# moire_brd_eagle7.net
KiCad netlist of a schematic drawn in EAGLE
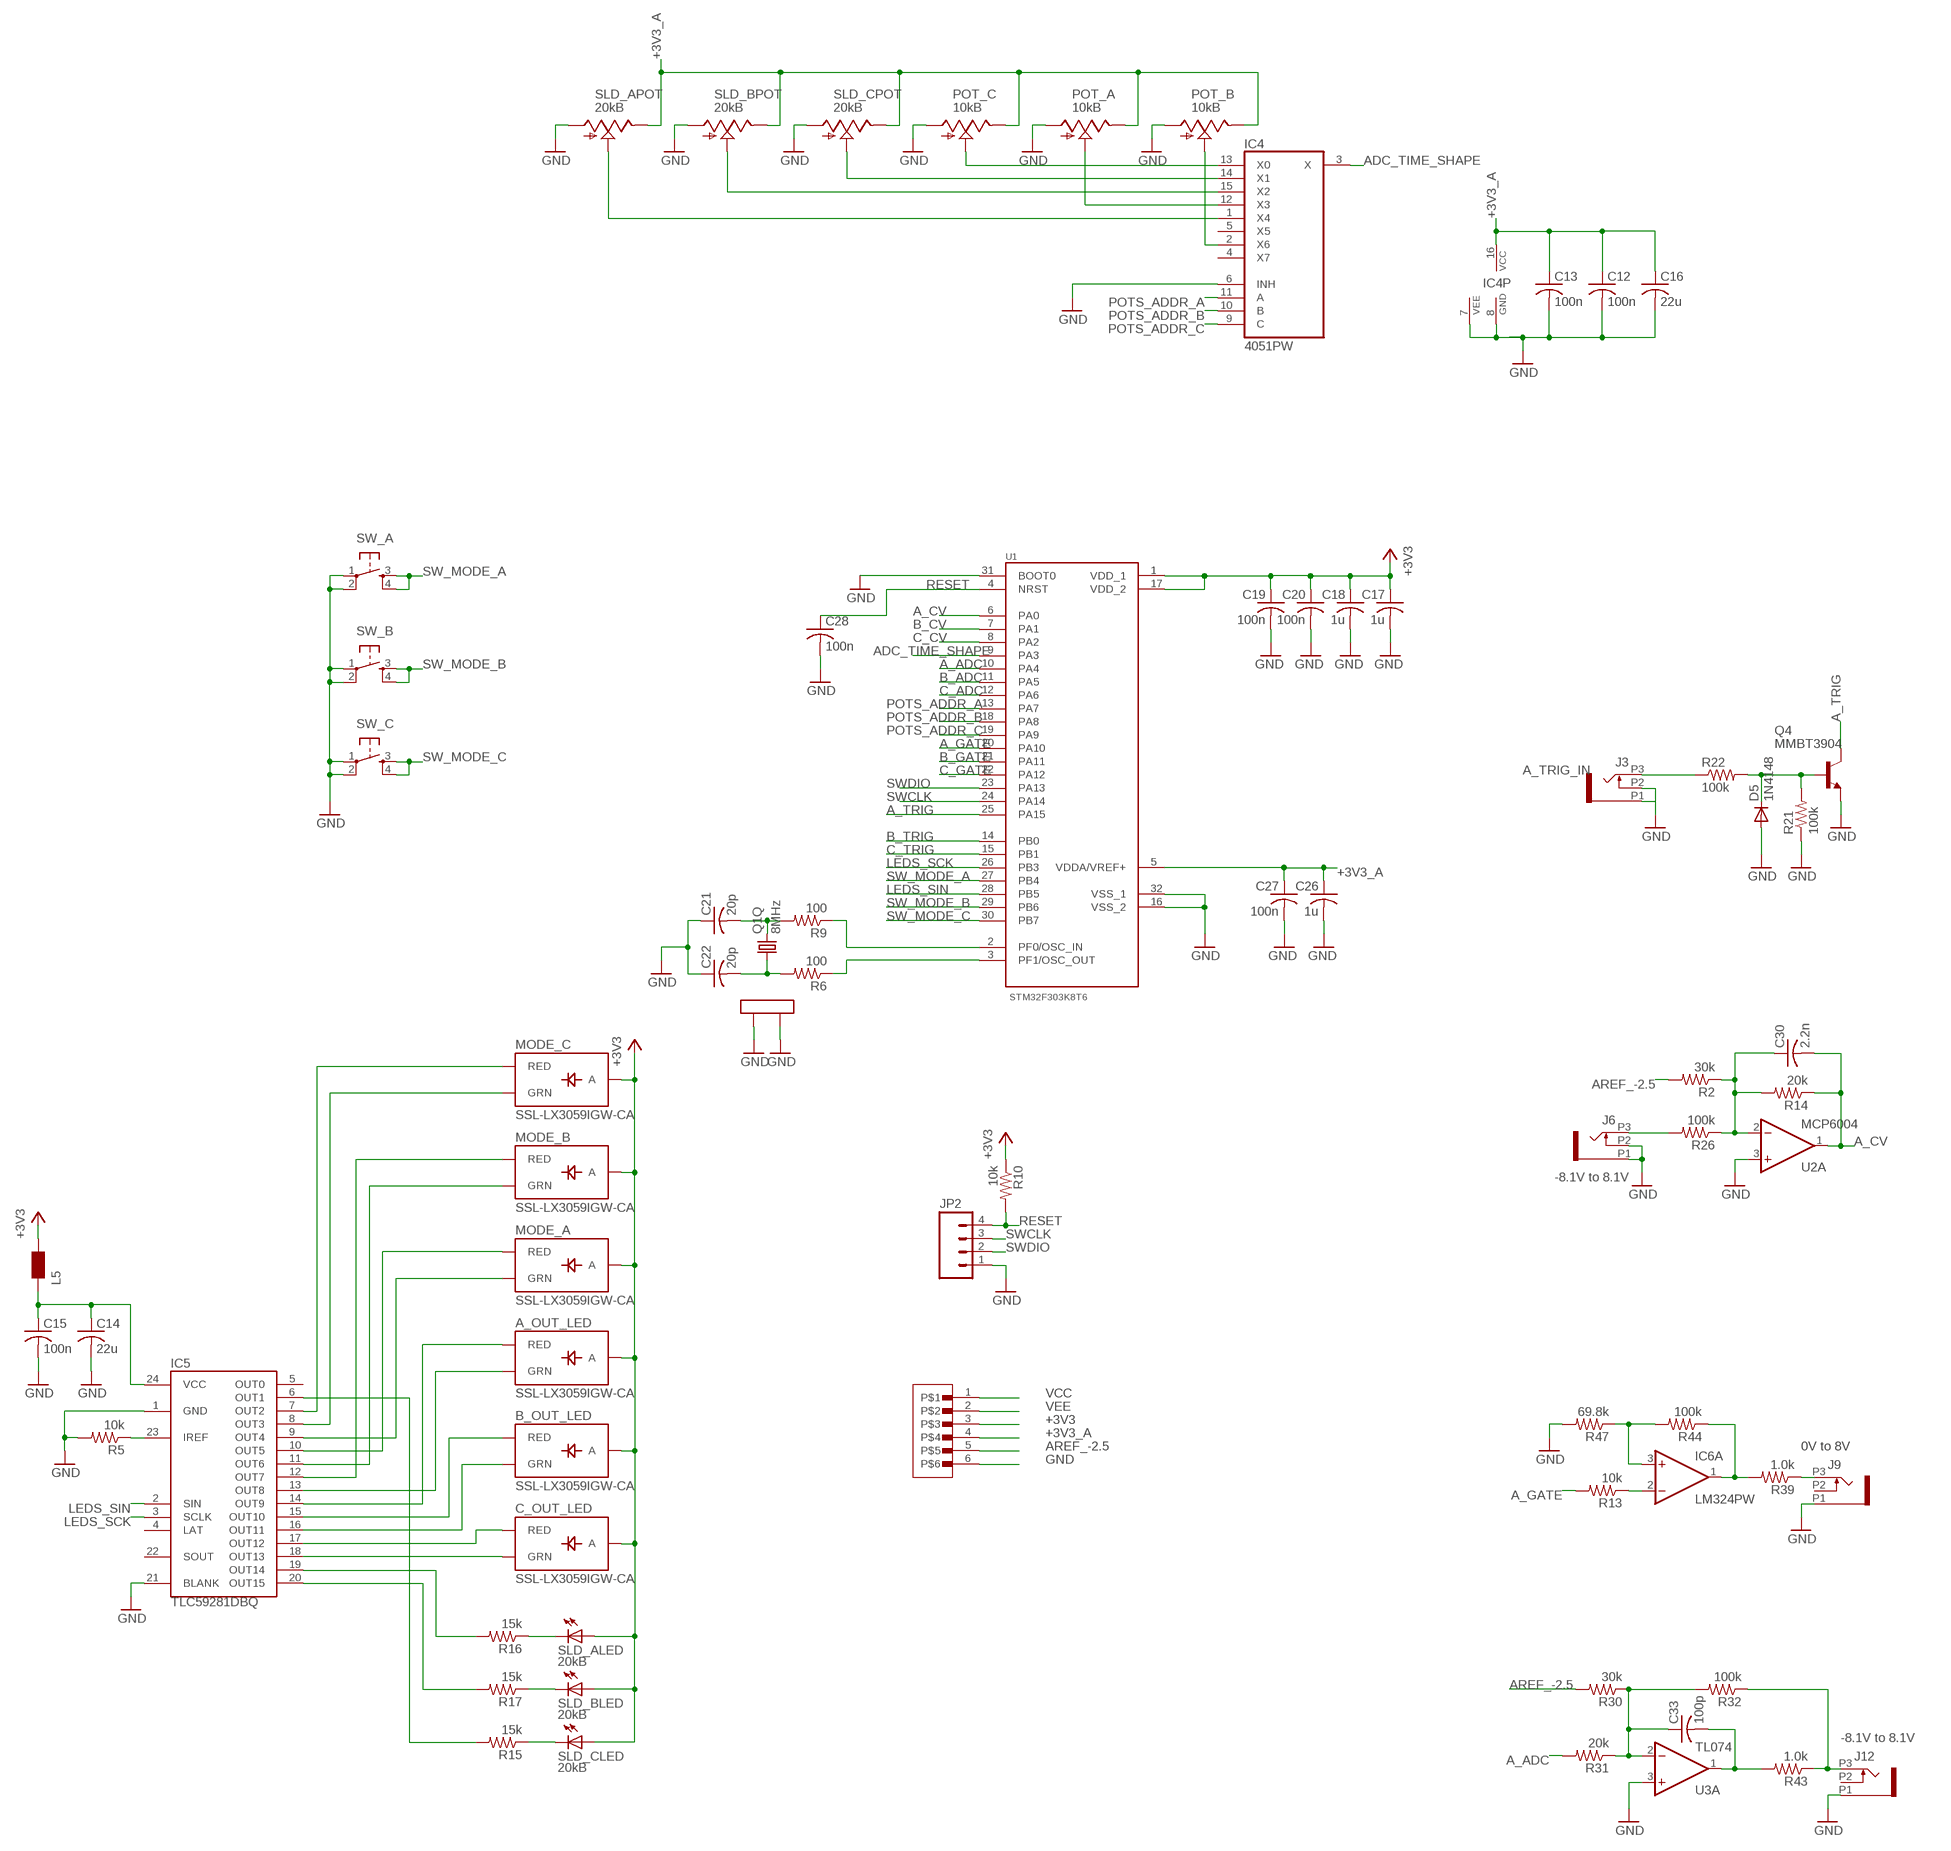
[diagram p0: schematic, sheet 1, part 1 of 2]
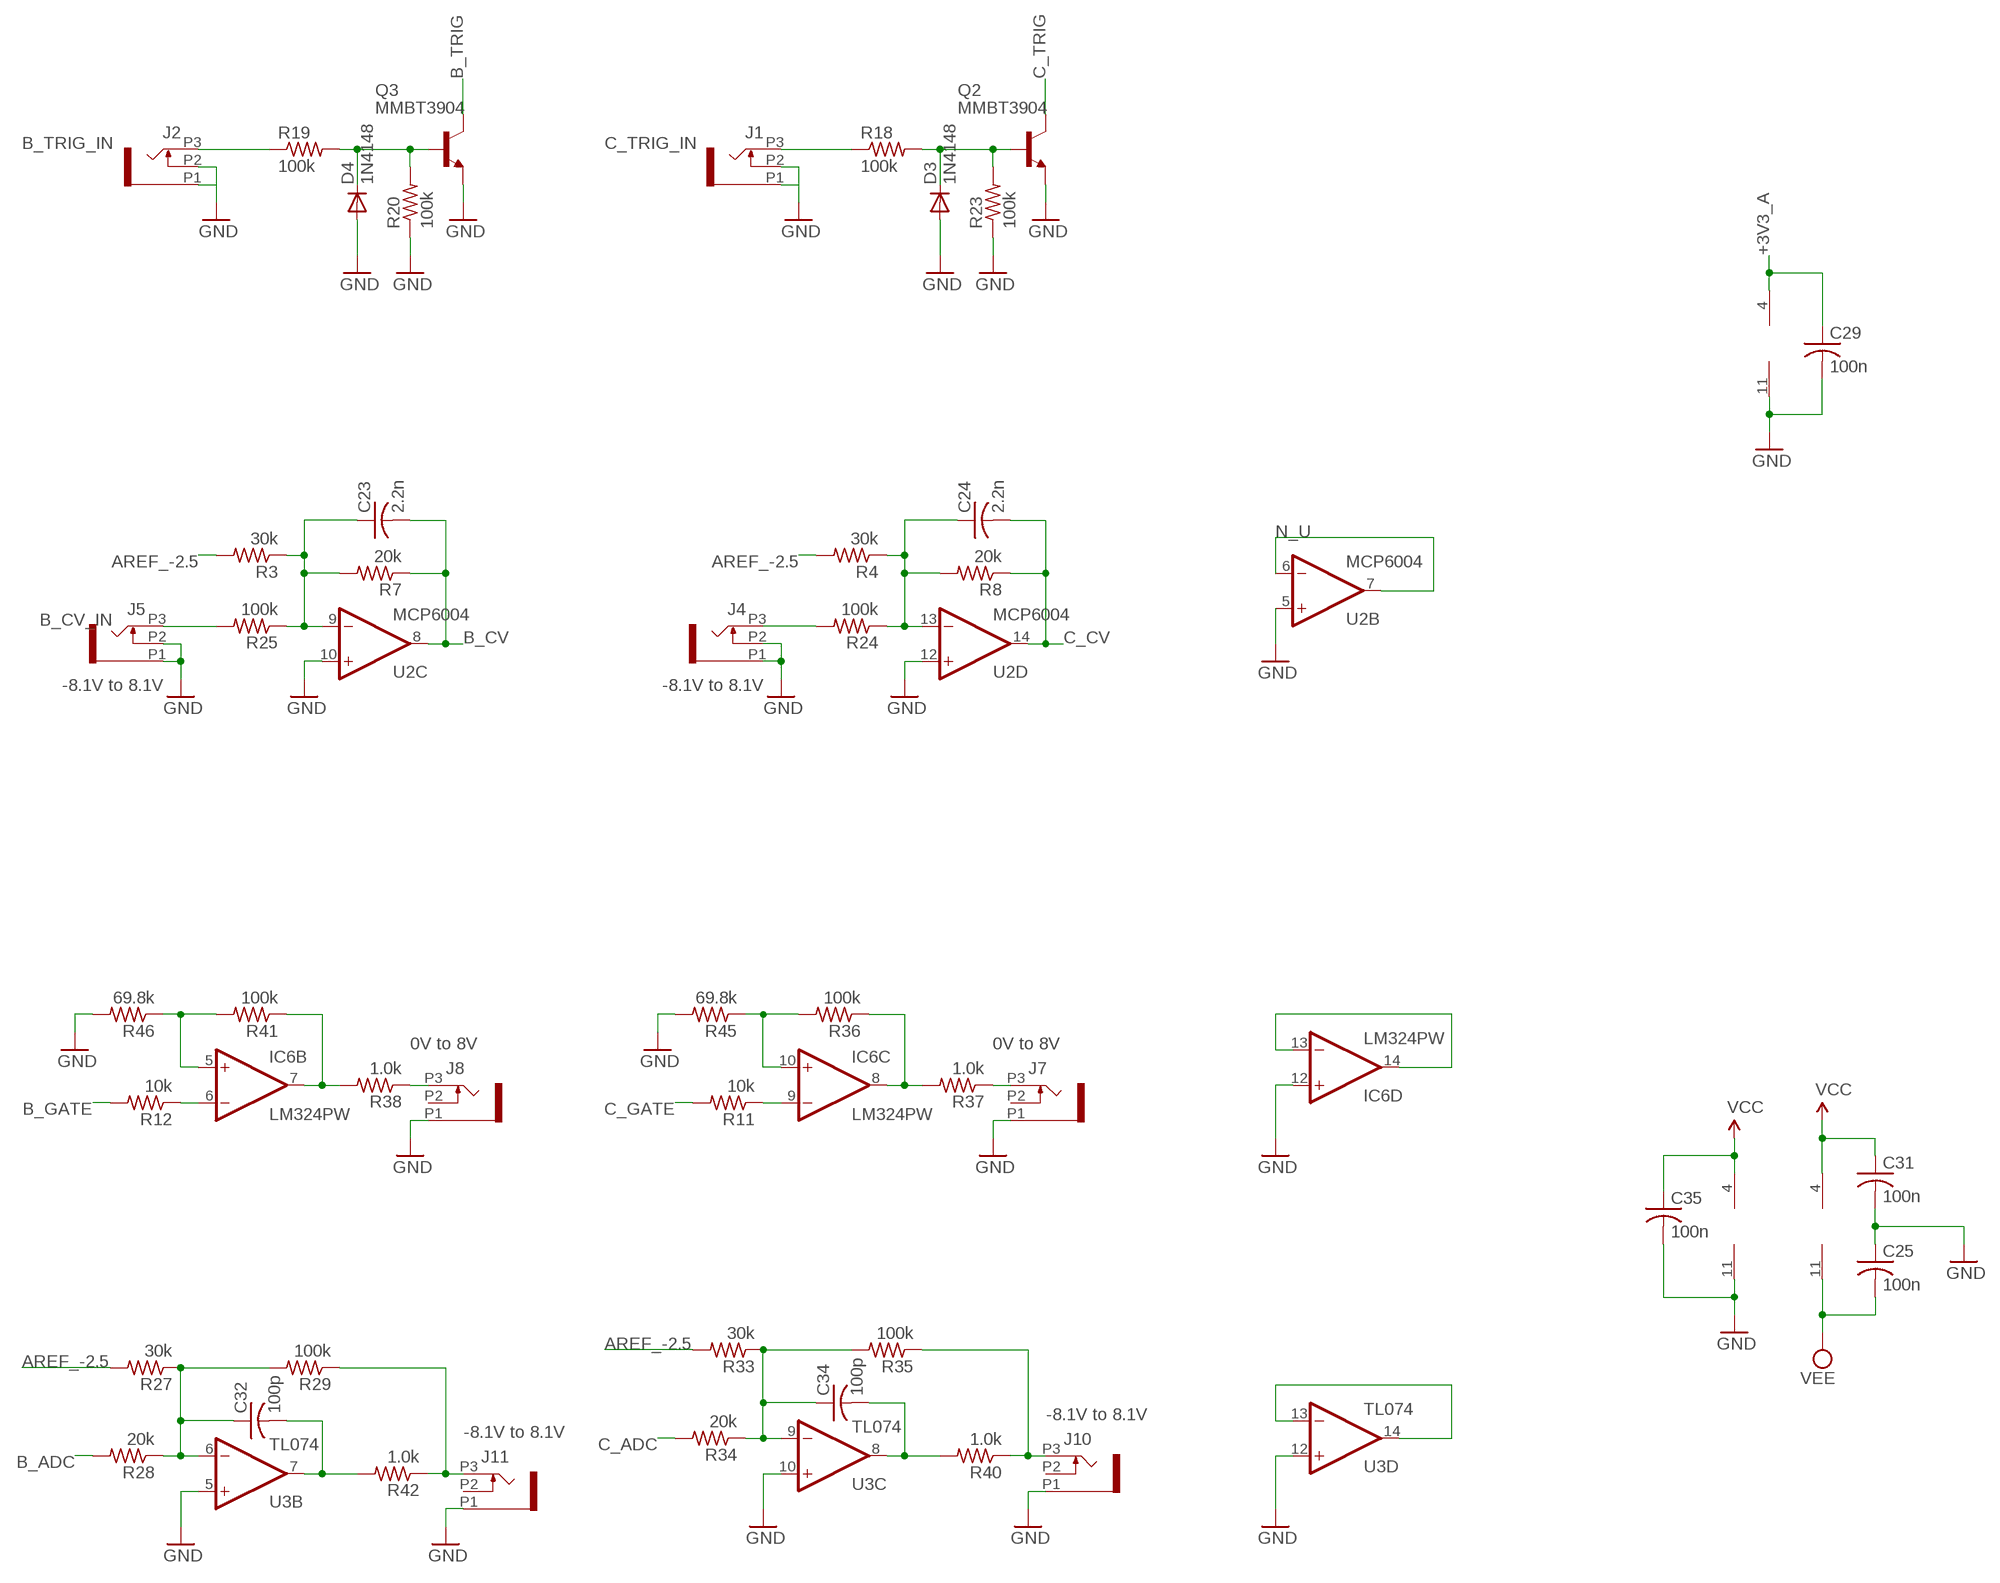
[diagram p1: schematic, sheet 1, part 2 of 2]
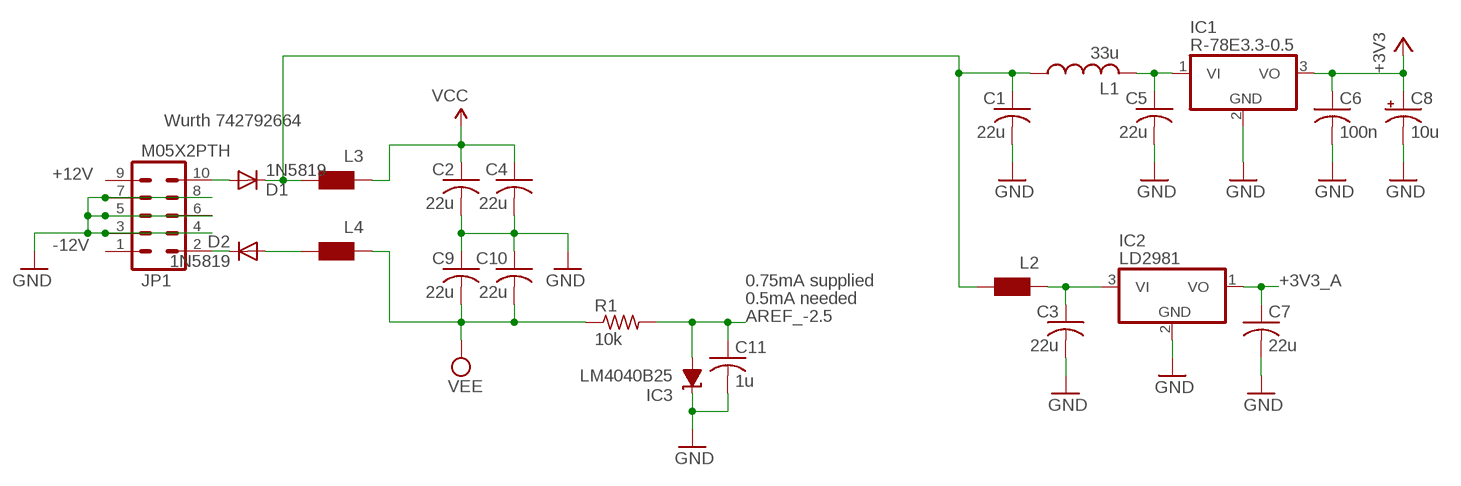
[diagram p2: schematic, sheet 2]

(export (version "E")
  (design (tool "Eeschema 10.0.6"))
  (components
    (comp (ref "A_OUT_LED")
      (value "SSL-LX3059IGW-CA")
      (footprint "eagle-import:LED-BICOLOR-THROUGHHOLE-LUMEX")
      (libsource (lib "eagle-import") (part "LED-BICOLOR-THROUGHHOLE-CA"))
    )
    (comp (ref "B_OUT_LED")
      (value "SSL-LX3059IGW-CA")
      (footprint "eagle-import:LED-BICOLOR-THROUGHHOLE-LUMEX")
      (libsource (lib "eagle-import") (part "LED-BICOLOR-THROUGHHOLE-CA"))
    )
    (comp (ref "C12")
      (value "100n")
      (footprint "eagle-import:RCL_C0603")
      (libsource (lib "eagle-import") (part "RCL_C-USC0603"))
    )
    (comp (ref "C13")
      (value "100n")
      (footprint "eagle-import:RCL_C0603")
      (libsource (lib "eagle-import") (part "RCL_C-USC0603"))
    )
    (comp (ref "C14")
      (value "22u")
      (footprint "eagle-import:RCL_C1206")
      (libsource (lib "eagle-import") (part "RCL_C-USC1206"))
    )
    (comp (ref "C15")
      (value "100n")
      (footprint "eagle-import:RCL_C0603")
      (libsource (lib "eagle-import") (part "RCL_C-USC0603"))
    )
    (comp (ref "C16")
      (value "22u")
      (footprint "eagle-import:RCL_C1206")
      (libsource (lib "eagle-import") (part "RCL_C-USC1206"))
    )
    (comp (ref "C17")
      (value "1u")
      (footprint "eagle-import:RCL_C0603")
      (libsource (lib "eagle-import") (part "RCL_C-USC0603"))
    )
    (comp (ref "C18")
      (value "1u")
      (footprint "eagle-import:RCL_C0603")
      (libsource (lib "eagle-import") (part "RCL_C-USC0603"))
    )
    (comp (ref "C19")
      (value "100n")
      (footprint "eagle-import:RCL_C0603")
      (libsource (lib "eagle-import") (part "RCL_C-USC0603"))
    )
    (comp (ref "C20")
      (value "100n")
      (footprint "eagle-import:RCL_C0603")
      (libsource (lib "eagle-import") (part "RCL_C-USC0603"))
    )
    (comp (ref "C21")
      (value "20p")
      (footprint "eagle-import:RCL_C0603")
      (libsource (lib "eagle-import") (part "RCL_C-USC0603"))
    )
    (comp (ref "C22")
      (value "20p")
      (footprint "eagle-import:RCL_C0603")
      (libsource (lib "eagle-import") (part "RCL_C-USC0603"))
    )
    (comp (ref "C23")
      (value "2.2n")
      (footprint "eagle-import:RCL_C0603")
      (libsource (lib "eagle-import") (part "RCL_C-USC0603"))
    )
    (comp (ref "C24")
      (value "2.2n")
      (footprint "eagle-import:RCL_C0603")
      (libsource (lib "eagle-import") (part "RCL_C-USC0603"))
    )
    (comp (ref "C25")
      (value "100n")
      (footprint "eagle-import:RCL_C0603")
      (libsource (lib "eagle-import") (part "RCL_C-USC0603"))
    )
    (comp (ref "C26")
      (value "1u")
      (footprint "eagle-import:RCL_C0603")
      (libsource (lib "eagle-import") (part "RCL_C-USC0603"))
    )
    (comp (ref "C27")
      (value "100n")
      (footprint "eagle-import:RCL_C0603")
      (libsource (lib "eagle-import") (part "RCL_C-USC0603"))
    )
    (comp (ref "C28")
      (value "100n")
      (footprint "eagle-import:RCL_C0603")
      (libsource (lib "eagle-import") (part "RCL_C-USC0603"))
    )
    (comp (ref "C29")
      (value "100n")
      (footprint "eagle-import:RCL_C0603")
      (libsource (lib "eagle-import") (part "RCL_C-USC0603"))
    )
    (comp (ref "C30")
      (value "2.2n")
      (footprint "eagle-import:RCL_C0603")
      (libsource (lib "eagle-import") (part "RCL_C-USC0603"))
    )
    (comp (ref "C31")
      (value "100n")
      (footprint "eagle-import:RCL_C0603")
      (libsource (lib "eagle-import") (part "RCL_C-USC0603"))
    )
    (comp (ref "C32")
      (value "100p")
      (footprint "eagle-import:RCL_C0603")
      (libsource (lib "eagle-import") (part "RCL_C-USC0603"))
    )
    (comp (ref "C33")
      (value "100p")
      (footprint "eagle-import:RCL_C0603")
      (libsource (lib "eagle-import") (part "RCL_C-USC0603"))
    )
    (comp (ref "C34")
      (value "100p")
      (footprint "eagle-import:RCL_C0603")
      (libsource (lib "eagle-import") (part "RCL_C-USC0603"))
    )
    (comp (ref "C35")
      (value "100n")
      (footprint "eagle-import:RCL_C0603")
      (libsource (lib "eagle-import") (part "RCL_C-USC0603"))
    )
    (comp (ref "C_OUT_LED")
      (value "SSL-LX3059IGW-CA")
      (footprint "eagle-import:LED-BICOLOR-THROUGHHOLE-LUMEX")
      (libsource (lib "eagle-import") (part "LED-BICOLOR-THROUGHHOLE-CA"))
    )
    (comp (ref "D3")
      (value "1N4148")
      (footprint "eagle-import:DIODE_SOD523")
      (libsource (lib "eagle-import") (part "DIODE_DIODE-SOD523"))
    )
    (comp (ref "D4")
      (value "1N4148")
      (footprint "eagle-import:DIODE_SOD523")
      (libsource (lib "eagle-import") (part "DIODE_DIODE-SOD523"))
    )
    (comp (ref "D5")
      (value "1N4148")
      (footprint "eagle-import:DIODE_SOD523")
      (libsource (lib "eagle-import") (part "DIODE_DIODE-SOD523"))
    )
    (comp (ref "IC4")
      (value "4051PW")
      (footprint "eagle-import:TSSOP16_065")
      (libsource (lib "eagle-import") (part "4051PW"))
    )
    (comp (ref "IC5")
      (value "TLC59281DBQ")
      (footprint "eagle-import:TSSOP24_0635")
      (libsource (lib "eagle-import") (part "TLC59281DBQ"))
    )
    (comp (ref "IC6")
      (value "LM324PW")
      (footprint "eagle-import:TSSOP14_065")
      (libsource (lib "eagle-import") (part "TL074PW"))
    )
    (comp (ref "J1")
      (value "PJ301_THONKICONN6")
      (footprint "eagle-import:WQP_PJ_301M6")
      (libsource (lib "eagle-import") (part "PJ301_THONKICONN6"))
    )
    (comp (ref "J2")
      (value "PJ301_THONKICONN6")
      (footprint "eagle-import:WQP_PJ_301M6")
      (libsource (lib "eagle-import") (part "PJ301_THONKICONN6"))
    )
    (comp (ref "J3")
      (value "PJ301_THONKICONN6")
      (footprint "eagle-import:WQP_PJ_301M6")
      (libsource (lib "eagle-import") (part "PJ301_THONKICONN6"))
    )
    (comp (ref "J4")
      (value "PJ301_THONKICONN6")
      (footprint "eagle-import:WQP_PJ_301M6")
      (libsource (lib "eagle-import") (part "PJ301_THONKICONN6"))
    )
    (comp (ref "J5")
      (value "PJ301_THONKICONN6")
      (footprint "eagle-import:WQP_PJ_301M6")
      (libsource (lib "eagle-import") (part "PJ301_THONKICONN6"))
    )
    (comp (ref "J6")
      (value "PJ301_THONKICONN6")
      (footprint "eagle-import:WQP_PJ_301M6")
      (libsource (lib "eagle-import") (part "PJ301_THONKICONN6"))
    )
    (comp (ref "J7")
      (value "PJ301_THONKICONN6")
      (footprint "eagle-import:WQP_PJ_301M6")
      (libsource (lib "eagle-import") (part "PJ301_THONKICONN6"))
    )
    (comp (ref "J8")
      (value "PJ301_THONKICONN6")
      (footprint "eagle-import:WQP_PJ_301M6")
      (libsource (lib "eagle-import") (part "PJ301_THONKICONN6"))
    )
    (comp (ref "J9")
      (value "PJ301_THONKICONN6")
      (footprint "eagle-import:WQP_PJ_301M6")
      (libsource (lib "eagle-import") (part "PJ301_THONKICONN6"))
    )
    (comp (ref "J10")
      (value "PJ301_THONKICONN6")
      (footprint "eagle-import:WQP_PJ_301M6")
      (libsource (lib "eagle-import") (part "PJ301_THONKICONN6"))
    )
    (comp (ref "J11")
      (value "PJ301_THONKICONN6")
      (footprint "eagle-import:WQP_PJ_301M6")
      (libsource (lib "eagle-import") (part "PJ301_THONKICONN6"))
    )
    (comp (ref "J12")
      (value "PJ301_THONKICONN6")
      (footprint "eagle-import:WQP_PJ_301M6")
      (libsource (lib "eagle-import") (part "PJ301_THONKICONN6"))
    )
    (comp (ref "JP2")
      (value "M04PTH")
      (footprint "eagle-import:1X04")
      (libsource (lib "eagle-import") (part "M04PTH"))
    )
    (comp (ref "L5")
      (value "WE-CBF_0603")
      (footprint "eagle-import:0603")
      (libsource (lib "eagle-import") (part "WE-CBF_0603"))
    )
    (comp (ref "MODE_A")
      (value "SSL-LX3059IGW-CA")
      (footprint "eagle-import:LED-BICOLOR-THROUGHHOLE-LUMEX")
      (libsource (lib "eagle-import") (part "LED-BICOLOR-THROUGHHOLE-CA"))
    )
    (comp (ref "MODE_B")
      (value "SSL-LX3059IGW-CA")
      (footprint "eagle-import:LED-BICOLOR-THROUGHHOLE-LUMEX")
      (libsource (lib "eagle-import") (part "LED-BICOLOR-THROUGHHOLE-CA"))
    )
    (comp (ref "MODE_C")
      (value "SSL-LX3059IGW-CA")
      (footprint "eagle-import:LED-BICOLOR-THROUGHHOLE-LUMEX")
      (libsource (lib "eagle-import") (part "LED-BICOLOR-THROUGHHOLE-CA"))
    )
    (comp (ref "POT_A")
      (value "10kB")
      (footprint "eagle-import:ALPS_POT_VERTICAL")
      (libsource (lib "eagle-import") (part "POT_USVERTICAL"))
    )
    (comp (ref "POT_B")
      (value "10kB")
      (footprint "eagle-import:ALPS_POT_VERTICAL")
      (libsource (lib "eagle-import") (part "POT_USVERTICAL"))
    )
    (comp (ref "POT_C")
      (value "10kB")
      (footprint "eagle-import:ALPS_POT_VERTICAL")
      (libsource (lib "eagle-import") (part "POT_USVERTICAL"))
    )
    (comp (ref "Q1")
      (value "8MHz")
      (footprint "eagle-import:CTS406")
      (libsource (lib "eagle-import") (part "CRYSTAL"))
    )
    (comp (ref "Q2")
      (value "MMBT3904")
      (footprint "eagle-import:SOT23-BEC")
      (libsource (lib "eagle-import") (part "-NPN-SOT23-BECMMBT3904LT1"))
    )
    (comp (ref "Q3")
      (value "MMBT3904")
      (footprint "eagle-import:SOT23-BEC")
      (libsource (lib "eagle-import") (part "-NPN-SOT23-BECMMBT3904LT1"))
    )
    (comp (ref "Q4")
      (value "MMBT3904")
      (footprint "eagle-import:SOT23-BEC")
      (libsource (lib "eagle-import") (part "-NPN-SOT23-BECMMBT3904LT1"))
    )
    (comp (ref "R2")
      (value "30k")
      (footprint "eagle-import:RCL_R0603")
      (libsource (lib "eagle-import") (part "RCL_R-US_R0603"))
    )
    (comp (ref "R3")
      (value "30k")
      (footprint "eagle-import:RCL_R0603")
      (libsource (lib "eagle-import") (part "RCL_R-US_R0603"))
    )
    (comp (ref "R4")
      (value "30k")
      (footprint "eagle-import:RCL_R0603")
      (libsource (lib "eagle-import") (part "RCL_R-US_R0603"))
    )
    (comp (ref "R5")
      (value "10k")
      (footprint "eagle-import:RCL_R0603")
      (libsource (lib "eagle-import") (part "RCL_R-US_R0603"))
    )
    (comp (ref "R6")
      (value "100")
      (footprint "eagle-import:RCL_R0603")
      (libsource (lib "eagle-import") (part "RCL_R-US_R0603"))
    )
    (comp (ref "R7")
      (value "20k")
      (footprint "eagle-import:RCL_R0603")
      (libsource (lib "eagle-import") (part "RCL_R-US_R0603"))
    )
    (comp (ref "R8")
      (value "20k")
      (footprint "eagle-import:RCL_R0603")
      (libsource (lib "eagle-import") (part "RCL_R-US_R0603"))
    )
    (comp (ref "R9")
      (value "100")
      (footprint "eagle-import:RCL_R0603")
      (libsource (lib "eagle-import") (part "RCL_R-US_R0603"))
    )
    (comp (ref "R10")
      (value "10k")
      (footprint "eagle-import:RCL_R0603")
      (libsource (lib "eagle-import") (part "RCL_R-US_R0603"))
    )
    (comp (ref "R11")
      (value "10k")
      (footprint "eagle-import:RCL_R0603")
      (libsource (lib "eagle-import") (part "RCL_R-US_R0603"))
    )
    (comp (ref "R12")
      (value "10k")
      (footprint "eagle-import:RCL_R0603")
      (libsource (lib "eagle-import") (part "RCL_R-US_R0603"))
    )
    (comp (ref "R13")
      (value "10k")
      (footprint "eagle-import:RCL_R0603")
      (libsource (lib "eagle-import") (part "RCL_R-US_R0603"))
    )
    (comp (ref "R14")
      (value "20k")
      (footprint "eagle-import:RCL_R0603")
      (libsource (lib "eagle-import") (part "RCL_R-US_R0603"))
    )
    (comp (ref "R15")
      (value "15k")
      (footprint "eagle-import:RCL_R0603")
      (libsource (lib "eagle-import") (part "RCL_R-US_R0603"))
    )
    (comp (ref "R16")
      (value "15k")
      (footprint "eagle-import:RCL_R0603")
      (libsource (lib "eagle-import") (part "RCL_R-US_R0603"))
    )
    (comp (ref "R17")
      (value "15k")
      (footprint "eagle-import:RCL_R0603")
      (libsource (lib "eagle-import") (part "RCL_R-US_R0603"))
    )
    (comp (ref "R18")
      (value "100k")
      (footprint "eagle-import:RCL_R0603")
      (libsource (lib "eagle-import") (part "RCL_R-US_R0603"))
    )
    (comp (ref "R19")
      (value "100k")
      (footprint "eagle-import:RCL_R0603")
      (libsource (lib "eagle-import") (part "RCL_R-US_R0603"))
    )
    (comp (ref "R20")
      (value "100k")
      (footprint "eagle-import:RCL_R0603")
      (libsource (lib "eagle-import") (part "RCL_R-US_R0603"))
    )
    (comp (ref "R21")
      (value "100k")
      (footprint "eagle-import:RCL_R0603")
      (libsource (lib "eagle-import") (part "RCL_R-US_R0603"))
    )
    (comp (ref "R22")
      (value "100k")
      (footprint "eagle-import:RCL_R0603")
      (libsource (lib "eagle-import") (part "RCL_R-US_R0603"))
    )
    (comp (ref "R23")
      (value "100k")
      (footprint "eagle-import:RCL_R0603")
      (libsource (lib "eagle-import") (part "RCL_R-US_R0603"))
    )
    (comp (ref "R24")
      (value "100k")
      (footprint "eagle-import:RCL_R0603")
      (libsource (lib "eagle-import") (part "RCL_R-US_R0603"))
    )
    (comp (ref "R25")
      (value "100k")
      (footprint "eagle-import:RCL_R0603")
      (libsource (lib "eagle-import") (part "RCL_R-US_R0603"))
    )
    (comp (ref "R26")
      (value "100k")
      (footprint "eagle-import:RCL_R0603")
      (libsource (lib "eagle-import") (part "RCL_R-US_R0603"))
    )
    (comp (ref "R27")
      (value "30k")
      (footprint "eagle-import:RCL_R0603")
      (libsource (lib "eagle-import") (part "RCL_R-US_R0603"))
    )
    (comp (ref "R28")
      (value "20k")
      (footprint "eagle-import:RCL_R0603")
      (libsource (lib "eagle-import") (part "RCL_R-US_R0603"))
    )
    (comp (ref "R29")
      (value "100k")
      (footprint "eagle-import:RCL_R0603")
      (libsource (lib "eagle-import") (part "RCL_R-US_R0603"))
    )
    (comp (ref "R30")
      (value "30k")
      (footprint "eagle-import:RCL_R0603")
      (libsource (lib "eagle-import") (part "RCL_R-US_R0603"))
    )
    (comp (ref "R31")
      (value "20k")
      (footprint "eagle-import:RCL_R0603")
      (libsource (lib "eagle-import") (part "RCL_R-US_R0603"))
    )
    (comp (ref "R32")
      (value "100k")
      (footprint "eagle-import:RCL_R0603")
      (libsource (lib "eagle-import") (part "RCL_R-US_R0603"))
    )
    (comp (ref "R33")
      (value "30k")
      (footprint "eagle-import:RCL_R0603")
      (libsource (lib "eagle-import") (part "RCL_R-US_R0603"))
    )
    (comp (ref "R34")
      (value "20k")
      (footprint "eagle-import:RCL_R0603")
      (libsource (lib "eagle-import") (part "RCL_R-US_R0603"))
    )
    (comp (ref "R35")
      (value "100k")
      (footprint "eagle-import:RCL_R0603")
      (libsource (lib "eagle-import") (part "RCL_R-US_R0603"))
    )
    (comp (ref "R36")
      (value "100k")
      (footprint "eagle-import:RCL_R0603")
      (libsource (lib "eagle-import") (part "RCL_R-US_R0603"))
    )
    (comp (ref "R37")
      (value "1.0k")
      (footprint "eagle-import:RCL_R0603")
      (libsource (lib "eagle-import") (part "RCL_R-US_R0603"))
    )
    (comp (ref "R38")
      (value "1.0k")
      (footprint "eagle-import:RCL_R0603")
      (libsource (lib "eagle-import") (part "RCL_R-US_R0603"))
    )
    (comp (ref "R39")
      (value "1.0k")
      (footprint "eagle-import:RCL_R0603")
      (libsource (lib "eagle-import") (part "RCL_R-US_R0603"))
    )
    (comp (ref "R40")
      (value "1.0k")
      (footprint "eagle-import:RCL_R0603")
      (libsource (lib "eagle-import") (part "RCL_R-US_R0603"))
    )
    (comp (ref "R41")
      (value "100k")
      (footprint "eagle-import:RCL_R0603")
      (libsource (lib "eagle-import") (part "RCL_R-US_R0603"))
    )
    (comp (ref "R42")
      (value "1.0k")
      (footprint "eagle-import:RCL_R0603")
      (libsource (lib "eagle-import") (part "RCL_R-US_R0603"))
    )
    (comp (ref "R43")
      (value "1.0k")
      (footprint "eagle-import:RCL_R0603")
      (libsource (lib "eagle-import") (part "RCL_R-US_R0603"))
    )
    (comp (ref "R44")
      (value "100k")
      (footprint "eagle-import:RCL_R0603")
      (libsource (lib "eagle-import") (part "RCL_R-US_R0603"))
    )
    (comp (ref "R45")
      (value "69.8k")
      (footprint "eagle-import:RCL_R0603")
      (libsource (lib "eagle-import") (part "RCL_R-US_R0603"))
    )
    (comp (ref "R46")
      (value "69.8k")
      (footprint "eagle-import:RCL_R0603")
      (libsource (lib "eagle-import") (part "RCL_R-US_R0603"))
    )
    (comp (ref "R47")
      (value "69.8k")
      (footprint "eagle-import:RCL_R0603")
      (libsource (lib "eagle-import") (part "RCL_R-US_R0603"))
    )
    (comp (ref "SLD_A")
      (value "20kB")
      (footprint "eagle-import:BOURNS_SLIDER")
      (libsource (lib "eagle-import") (part "BOURNS_SLIDER"))
    )
    (comp (ref "SLD_B")
      (value "20kB")
      (footprint "eagle-import:BOURNS_SLIDER")
      (libsource (lib "eagle-import") (part "BOURNS_SLIDER"))
    )
    (comp (ref "SLD_C")
      (value "20kB")
      (footprint "eagle-import:BOURNS_SLIDER")
      (libsource (lib "eagle-import") (part "BOURNS_SLIDER"))
    )
    (comp (ref "SW_A")
      (value "TAC_SWITCHPTH")
      (footprint "eagle-import:TACTILE-PTH")
      (libsource (lib "eagle-import") (part "TAC_SWITCHPTH"))
    )
    (comp (ref "SW_B")
      (value "TAC_SWITCHPTH")
      (footprint "eagle-import:TACTILE-PTH")
      (libsource (lib "eagle-import") (part "TAC_SWITCHPTH"))
    )
    (comp (ref "SW_C")
      (value "TAC_SWITCHPTH")
      (footprint "eagle-import:TACTILE-PTH")
      (libsource (lib "eagle-import") (part "TAC_SWITCHPTH"))
    )
    (comp (ref "U$1")
      (value "1X6-SMD-TESTPAD")
      (footprint "eagle-import:6X1-SMD-TESTPAD")
      (libsource (lib "eagle-import") (part "1X6-SMD-TESTPAD"))
    )
    (comp (ref "U1")
      (value "STM32F303K8T6")
      (footprint "eagle-import:QFP80P900X900X160-32N")
      (fields (field (name "MF") "STMicroelectronics"))
      (libsource (lib "eagle-import") (part "STM32F303K8T6"))
    )
    (comp (ref "U2")
      (value "MCP6004")
      (footprint "eagle-import:SO14")
      (libsource (lib "eagle-import") (part "MCP6004_SMD"))
    )
    (comp (ref "U3")
      (value "TL074")
      (footprint "eagle-import:SO14")
      (libsource (lib "eagle-import") (part "TL074_SMD"))
    )
    (comp (ref "C1")
      (value "22u")
      (footprint "eagle-import:RCL_C1206")
      (libsource (lib "eagle-import") (part "RCL_C-USC1206"))
    )
    (comp (ref "C2")
      (value "22u")
      (footprint "eagle-import:RCL_C1206")
      (libsource (lib "eagle-import") (part "RCL_C-USC1206"))
    )
    (comp (ref "C3")
      (value "22u")
      (footprint "eagle-import:RCL_C1206")
      (libsource (lib "eagle-import") (part "RCL_C-USC1206"))
    )
    (comp (ref "C4")
      (value "22u")
      (footprint "eagle-import:RCL_C1206")
      (libsource (lib "eagle-import") (part "RCL_C-USC1206"))
    )
    (comp (ref "C5")
      (value "22u")
      (footprint "eagle-import:RCL_C1206")
      (libsource (lib "eagle-import") (part "RCL_C-USC1206"))
    )
    (comp (ref "C6")
      (value "100n")
      (footprint "eagle-import:RCL_C0603")
      (libsource (lib "eagle-import") (part "RCL_C-USC0603"))
    )
    (comp (ref "C7")
      (value "22u")
      (footprint "eagle-import:RCL_C1206")
      (libsource (lib "eagle-import") (part "RCL_C-USC1206"))
    )
    (comp (ref "C8")
      (value "10u")
      (footprint "eagle-import:RCL_PANASONIC_A")
      (libsource (lib "eagle-import") (part "RCL_CPOL-USA"))
    )
    (comp (ref "C9")
      (value "22u")
      (footprint "eagle-import:RCL_C1206")
      (libsource (lib "eagle-import") (part "RCL_C-USC1206"))
    )
    (comp (ref "C10")
      (value "22u")
      (footprint "eagle-import:RCL_C1206")
      (libsource (lib "eagle-import") (part "RCL_C-USC1206"))
    )
    (comp (ref "C11")
      (value "1u")
      (footprint "eagle-import:RCL_C0603")
      (libsource (lib "eagle-import") (part "RCL_C-USC0603"))
    )
    (comp (ref "D1")
      (value "1N5819")
      (footprint "eagle-import:DIODE_SOD123")
      (libsource (lib "eagle-import") (part "DIODE_DIODE-SOD123"))
    )
    (comp (ref "D2")
      (value "1N5819")
      (footprint "eagle-import:DIODE_SOD123")
      (libsource (lib "eagle-import") (part "DIODE_DIODE-SOD123"))
    )
    (comp (ref "IC1")
      (value "R-78E3.3-0.5")
      (footprint "eagle-import:WE78")
      (libsource (lib "eagle-import") (part "WE173950378"))
    )
    (comp (ref "IC2")
      (value "LD2981")
      (footprint "eagle-import:SOT89")
      (libsource (lib "eagle-import") (part "LD2981ABU"))
    )
    (comp (ref "IC3")
      (value "LM4040B25")
      (footprint "eagle-import:DBZ_R-PDSO-G3")
      (libsource (lib "eagle-import") (part "LM4041DBZB12"))
    )
    (comp (ref "JP1")
      (value "M05X2PTH")
      (footprint "eagle-import:2X5-PTH")
      (libsource (lib "eagle-import") (part "M05X2PTH"))
    )
    (comp (ref "L1")
      (value "33u")
      (footprint "eagle-import:L2012C")
      (libsource (lib "eagle-import") (part "L-USL2012C"))
    )
    (comp (ref "L2")
      (value "WE-CBF_0603")
      (footprint "eagle-import:0603")
      (libsource (lib "eagle-import") (part "WE-CBF_0603"))
    )
    (comp (ref "L3")
      (value "WE-CBF_0603")
      (footprint "eagle-import:0603")
      (libsource (lib "eagle-import") (part "WE-CBF_0603"))
    )
    (comp (ref "L4")
      (value "WE-CBF_0603")
      (footprint "eagle-import:0603")
      (libsource (lib "eagle-import") (part "WE-CBF_0603"))
    )
    (comp (ref "R1")
      (value "10k")
      (footprint "eagle-import:RCL_R0603")
      (libsource (lib "eagle-import") (part "RCL_R-US_R0603"))
    )
  )
  (nets
    (net (code "1") (name "+3V3") (class "Default")
      (node (ref "A_OUT_LED") (pin "A") (pinfunction "A_A") (pintype "bidirectional"))
      (node (ref "B_OUT_LED") (pin "A") (pinfunction "A_A") (pintype "bidirectional"))
      (node (ref "C17") (pin "1") (pinfunction "1_1") (pintype "passive"))
      (node (ref "C18") (pin "1") (pinfunction "1_1") (pintype "passive"))
      (node (ref "C19") (pin "1") (pinfunction "1_1") (pintype "passive"))
      (node (ref "C20") (pin "1") (pinfunction "1_1") (pintype "passive"))
      (node (ref "C6") (pin "1") (pinfunction "1_1") (pintype "passive"))
      (node (ref "C8") (pin "+") (pinfunction "+_+") (pintype "passive"))
      (node (ref "C_OUT_LED") (pin "A") (pinfunction "A_A") (pintype "bidirectional"))
      (node (ref "IC1") (pin "3") (pinfunction "VO_3") (pintype "passive"))
      (node (ref "L5") (pin "2") (pinfunction "2_2") (pintype "passive"))
      (node (ref "MODE_A") (pin "A") (pinfunction "A_A") (pintype "bidirectional"))
      (node (ref "MODE_B") (pin "A") (pinfunction "A_A") (pintype "bidirectional"))
      (node (ref "MODE_C") (pin "A") (pinfunction "A_A") (pintype "bidirectional"))
      (node (ref "R10") (pin "1") (pinfunction "1_1") (pintype "passive"))
      (node (ref "SLD_A") (pin "B") (pinfunction "A_B") (pintype "passive"))
      (node (ref "SLD_B") (pin "B") (pinfunction "A_B") (pintype "passive"))
      (node (ref "SLD_C") (pin "B") (pinfunction "A_B") (pintype "passive"))
      (node (ref "U$1") (pin "3") (pinfunction "P$3_3") (pintype "bidirectional"))
      (node (ref "U1") (pin "1") (pinfunction "VDD_1_1") (pintype "power_in"))
      (node (ref "U1") (pin "17") (pinfunction "VDD_2_17") (pintype "power_in"))
    )
    (net (code "2") (name "+3V3_A") (class "Default")
      (node (ref "C12") (pin "1") (pinfunction "1_1") (pintype "passive"))
      (node (ref "C13") (pin "1") (pinfunction "1_1") (pintype "passive"))
      (node (ref "C16") (pin "1") (pinfunction "1_1") (pintype "passive"))
      (node (ref "C26") (pin "1") (pinfunction "1_1") (pintype "passive"))
      (node (ref "C27") (pin "1") (pinfunction "1_1") (pintype "passive"))
      (node (ref "C29") (pin "1") (pinfunction "1_1") (pintype "passive"))
      (node (ref "C7") (pin "1") (pinfunction "1_1") (pintype "passive"))
      (node (ref "IC2") (pin "1") (pinfunction "VO_1") (pintype "passive"))
      (node (ref "IC4") (pin "16") (pinfunction "VCC_16") (pintype "power_in"))
      (node (ref "POT_A") (pin "P$1") (pinfunction "E_P$1") (pintype "passive"))
      (node (ref "POT_B") (pin "P$1") (pinfunction "E_P$1") (pintype "passive"))
      (node (ref "POT_C") (pin "P$1") (pinfunction "E_P$1") (pintype "passive"))
      (node (ref "SLD_A") (pin "3") (pinfunction "E_3") (pintype "passive"))
      (node (ref "SLD_B") (pin "3") (pinfunction "E_3") (pintype "passive"))
      (node (ref "SLD_C") (pin "3") (pinfunction "E_3") (pintype "passive"))
      (node (ref "U$1") (pin "4") (pinfunction "P$4_4") (pintype "bidirectional"))
      (node (ref "U1") (pin "5") (pinfunction "VDDA/VREF+_5") (pintype "power_in"))
      (node (ref "U2") (pin "4") (pinfunction "V+_4") (pintype "power_in"))
    )
    (net (code "3") (name "+12V") (class "Default")
      (node (ref "D1") (pin "A") (pinfunction "A_A") (pintype "passive"))
      (node (ref "JP1") (pin "10") (pinfunction "10_10") (pintype "passive"))
      (node (ref "JP1") (pin "9") (pinfunction "9_9") (pintype "passive"))
    )
    (net (code "4") (name "-12V") (class "Default")
      (node (ref "D2") (pin "C") (pinfunction "C_C") (pintype "passive"))
      (node (ref "JP1") (pin "1") (pinfunction "1_1") (pintype "passive"))
      (node (ref "JP1") (pin "2") (pinfunction "2_2") (pintype "passive"))
    )
    (net (code "5") (name "ADC_TIME_SHAPE") (class "Default")
      (node (ref "IC4") (pin "3") (pinfunction "X_3") (pintype "bidirectional"))
      (node (ref "U1") (pin "9") (pinfunction "PA3_9") (pintype "bidirectional"))
    )
    (net (code "6") (name "AREF_-2.5") (class "Default")
      (node (ref "C11") (pin "1") (pinfunction "1_1") (pintype "passive"))
      (node (ref "IC3") (pin "2") (pinfunction "A_2") (pintype "passive"))
      (node (ref "R1") (pin "2") (pinfunction "2_2") (pintype "passive"))
      (node (ref "R2") (pin "2") (pinfunction "2_2") (pintype "passive"))
      (node (ref "R27") (pin "2") (pinfunction "2_2") (pintype "passive"))
      (node (ref "R3") (pin "2") (pinfunction "2_2") (pintype "passive"))
      (node (ref "R30") (pin "2") (pinfunction "2_2") (pintype "passive"))
      (node (ref "R33") (pin "2") (pinfunction "2_2") (pintype "passive"))
      (node (ref "R4") (pin "2") (pinfunction "2_2") (pintype "passive"))
      (node (ref "U$1") (pin "5") (pinfunction "P$5_5") (pintype "bidirectional"))
    )
    (net (code "7") (name "A_ADC") (class "Default")
      (node (ref "R31") (pin "2") (pinfunction "2_2") (pintype "passive"))
      (node (ref "U1") (pin "10") (pinfunction "PA4_10") (pintype "bidirectional"))
    )
    (net (code "8") (name "A_CV") (class "Default")
      (node (ref "C30") (pin "2") (pinfunction "2_2") (pintype "passive"))
      (node (ref "R14") (pin "1") (pinfunction "1_1") (pintype "passive"))
      (node (ref "U1") (pin "6") (pinfunction "PA0_6") (pintype "bidirectional"))
      (node (ref "U2") (pin "1") (pinfunction "OUT_1") (pintype "output"))
    )
    (net (code "9") (name "A_GATE") (class "Default")
      (node (ref "R13") (pin "2") (pinfunction "2_2") (pintype "passive"))
      (node (ref "U1") (pin "20") (pinfunction "PA10_20") (pintype "bidirectional"))
    )
    (net (code "10") (name "A_TRIG") (class "Default")
      (node (ref "Q4") (pin "C") (pinfunction "C_C") (pintype "passive"))
      (node (ref "U1") (pin "25") (pinfunction "PA15_25") (pintype "bidirectional"))
    )
    (net (code "11") (name "A_TRIG_IN") (class "Default")
      (node (ref "J3") (pin "P3") (pinfunction "3_P3") (pintype "passive"))
      (node (ref "R22") (pin "1") (pinfunction "1_1") (pintype "passive"))
    )
    (net (code "12") (name "B_ADC") (class "Default")
      (node (ref "R28") (pin "2") (pinfunction "2_2") (pintype "passive"))
      (node (ref "U1") (pin "11") (pinfunction "PA5_11") (pintype "bidirectional"))
    )
    (net (code "13") (name "B_CV") (class "Default")
      (node (ref "C23") (pin "2") (pinfunction "2_2") (pintype "passive"))
      (node (ref "R7") (pin "1") (pinfunction "1_1") (pintype "passive"))
      (node (ref "U1") (pin "7") (pinfunction "PA1_7") (pintype "bidirectional"))
      (node (ref "U2") (pin "8") (pinfunction "OUT_8") (pintype "output"))
    )
    (net (code "14") (name "B_CV_IN") (class "Default")
      (node (ref "J5") (pin "P3") (pinfunction "3_P3") (pintype "passive"))
      (node (ref "R25") (pin "2") (pinfunction "2_2") (pintype "passive"))
    )
    (net (code "15") (name "B_GATE") (class "Default")
      (node (ref "R12") (pin "2") (pinfunction "2_2") (pintype "passive"))
      (node (ref "U1") (pin "21") (pinfunction "PA11_21") (pintype "bidirectional"))
    )
    (net (code "16") (name "B_TRIG") (class "Default")
      (node (ref "Q3") (pin "C") (pinfunction "C_C") (pintype "passive"))
      (node (ref "U1") (pin "14") (pinfunction "PB0_14") (pintype "bidirectional"))
    )
    (net (code "17") (name "B_TRIG_IN") (class "Default")
      (node (ref "J2") (pin "P3") (pinfunction "3_P3") (pintype "passive"))
      (node (ref "R19") (pin "1") (pinfunction "1_1") (pintype "passive"))
    )
    (net (code "18") (name "C_ADC") (class "Default")
      (node (ref "R34") (pin "2") (pinfunction "2_2") (pintype "passive"))
      (node (ref "U1") (pin "12") (pinfunction "PA6_12") (pintype "bidirectional"))
    )
    (net (code "19") (name "C_CV") (class "Default")
      (node (ref "C24") (pin "2") (pinfunction "2_2") (pintype "passive"))
      (node (ref "R8") (pin "1") (pinfunction "1_1") (pintype "passive"))
      (node (ref "U1") (pin "8") (pinfunction "PA2_8") (pintype "bidirectional"))
      (node (ref "U2") (pin "14") (pinfunction "OUT_14") (pintype "output"))
    )
    (net (code "20") (name "C_GATE") (class "Default")
      (node (ref "R11") (pin "2") (pinfunction "2_2") (pintype "passive"))
      (node (ref "U1") (pin "22") (pinfunction "PA12_22") (pintype "bidirectional"))
    )
    (net (code "21") (name "C_TRIG") (class "Default")
      (node (ref "Q2") (pin "C") (pinfunction "C_C") (pintype "passive"))
      (node (ref "U1") (pin "15") (pinfunction "PB1_15") (pintype "bidirectional"))
    )
    (net (code "22") (name "C_TRIG_IN") (class "Default")
      (node (ref "J1") (pin "P3") (pinfunction "3_P3") (pintype "passive"))
      (node (ref "R18") (pin "1") (pinfunction "1_1") (pintype "passive"))
    )
    (net (code "23") (name "GND") (class "Default")
      (node (ref "C1") (pin "2") (pinfunction "2_2") (pintype "passive"))
      (node (ref "C10") (pin "1") (pinfunction "1_1") (pintype "passive"))
      (node (ref "C11") (pin "2") (pinfunction "2_2") (pintype "passive"))
      (node (ref "C12") (pin "2") (pinfunction "2_2") (pintype "passive"))
      (node (ref "C13") (pin "2") (pinfunction "2_2") (pintype "passive"))
      (node (ref "C14") (pin "2") (pinfunction "2_2") (pintype "passive"))
      (node (ref "C15") (pin "2") (pinfunction "2_2") (pintype "passive"))
      (node (ref "C16") (pin "2") (pinfunction "2_2") (pintype "passive"))
      (node (ref "C17") (pin "2") (pinfunction "2_2") (pintype "passive"))
      (node (ref "C18") (pin "2") (pinfunction "2_2") (pintype "passive"))
      (node (ref "C19") (pin "2") (pinfunction "2_2") (pintype "passive"))
      (node (ref "C2") (pin "2") (pinfunction "2_2") (pintype "passive"))
      (node (ref "C20") (pin "2") (pinfunction "2_2") (pintype "passive"))
      (node (ref "C21") (pin "1") (pinfunction "1_1") (pintype "passive"))
      (node (ref "C22") (pin "1") (pinfunction "1_1") (pintype "passive"))
      (node (ref "C25") (pin "1") (pinfunction "1_1") (pintype "passive"))
      (node (ref "C26") (pin "2") (pinfunction "2_2") (pintype "passive"))
      (node (ref "C27") (pin "2") (pinfunction "2_2") (pintype "passive"))
      (node (ref "C28") (pin "2") (pinfunction "2_2") (pintype "passive"))
      (node (ref "C29") (pin "2") (pinfunction "2_2") (pintype "passive"))
      (node (ref "C3") (pin "2") (pinfunction "2_2") (pintype "passive"))
      (node (ref "C31") (pin "2") (pinfunction "2_2") (pintype "passive"))
      (node (ref "C35") (pin "2") (pinfunction "2_2") (pintype "passive"))
      (node (ref "C4") (pin "2") (pinfunction "2_2") (pintype "passive"))
      (node (ref "C5") (pin "2") (pinfunction "2_2") (pintype "passive"))
      (node (ref "C6") (pin "2") (pinfunction "2_2") (pintype "passive"))
      (node (ref "C7") (pin "2") (pinfunction "2_2") (pintype "passive"))
      (node (ref "C8") (pin "-") (pinfunction "-_-") (pintype "passive"))
      (node (ref "C9") (pin "1") (pinfunction "1_1") (pintype "passive"))
      (node (ref "D3") (pin "A") (pinfunction "A_A") (pintype "passive"))
      (node (ref "D4") (pin "A") (pinfunction "A_A") (pintype "passive"))
      (node (ref "D5") (pin "A") (pinfunction "A_A") (pintype "passive"))
      (node (ref "IC1") (pin "2") (pinfunction "GND_2") (pintype "passive"))
      (node (ref "IC2") (pin "2") (pinfunction "GND_2") (pintype "passive"))
      (node (ref "IC3") (pin "1") (pinfunction "C_1") (pintype "passive"))
      (node (ref "IC4") (pin "6") (pinfunction "INH_6") (pintype "input"))
      (node (ref "IC4") (pin "7") (pinfunction "VEE_7") (pintype "power_in"))
      (node (ref "IC4") (pin "8") (pinfunction "GND_8") (pintype "power_in"))
      (node (ref "IC5") (pin "1") (pinfunction "GND_1") (pintype "bidirectional"))
      (node (ref "IC5") (pin "21") (pinfunction "BLANK_21") (pintype "bidirectional"))
      (node (ref "IC6") (pin "11") (pinfunction "V-_11") (pintype "power_in"))
      (node (ref "IC6") (pin "12") (pinfunction "+IN_12") (pintype "input"))
      (node (ref "J1") (pin "P1") (pinfunction "1_P1") (pintype "passive"))
      (node (ref "J1") (pin "P2") (pinfunction "2_P2") (pintype "passive"))
      (node (ref "J10") (pin "P1") (pinfunction "1_P1") (pintype "passive"))
      (node (ref "J11") (pin "P1") (pinfunction "1_P1") (pintype "passive"))
      (node (ref "J12") (pin "P1") (pinfunction "1_P1") (pintype "passive"))
      (node (ref "J2") (pin "P1") (pinfunction "1_P1") (pintype "passive"))
      (node (ref "J2") (pin "P2") (pinfunction "2_P2") (pintype "passive"))
      (node (ref "J3") (pin "P1") (pinfunction "1_P1") (pintype "passive"))
      (node (ref "J3") (pin "P2") (pinfunction "2_P2") (pintype "passive"))
      (node (ref "J4") (pin "P1") (pinfunction "1_P1") (pintype "passive"))
      (node (ref "J4") (pin "P2") (pinfunction "2_P2") (pintype "passive"))
      (node (ref "J5") (pin "P1") (pinfunction "1_P1") (pintype "passive"))
      (node (ref "J5") (pin "P2") (pinfunction "2_P2") (pintype "passive"))
      (node (ref "J6") (pin "P1") (pinfunction "1_P1") (pintype "passive"))
      (node (ref "J6") (pin "P2") (pinfunction "2_P2") (pintype "passive"))
      (node (ref "J7") (pin "P1") (pinfunction "1_P1") (pintype "passive"))
      (node (ref "J8") (pin "P1") (pinfunction "1_P1") (pintype "passive"))
      (node (ref "J9") (pin "P1") (pinfunction "1_P1") (pintype "passive"))
      (node (ref "JP1") (pin "3") (pinfunction "3_3") (pintype "passive"))
      (node (ref "JP1") (pin "4") (pinfunction "4_4") (pintype "passive"))
      (node (ref "JP1") (pin "5") (pinfunction "5_5") (pintype "passive"))
      (node (ref "JP1") (pin "6") (pinfunction "6_6") (pintype "passive"))
      (node (ref "JP1") (pin "7") (pinfunction "7_7") (pintype "passive"))
      (node (ref "JP1") (pin "8") (pinfunction "8_8") (pintype "passive"))
      (node (ref "JP2") (pin "1") (pinfunction "1_1") (pintype "passive"))
      (node (ref "POT_A") (pin "P$3") (pinfunction "A_P$3") (pintype "passive"))
      (node (ref "POT_B") (pin "P$3") (pinfunction "A_P$3") (pintype "passive"))
      (node (ref "POT_C") (pin "P$3") (pinfunction "A_P$3") (pintype "passive"))
      (node (ref "Q1") (pin "2") (pinfunction "LID1_2") (pintype "power_in"))
      (node (ref "Q1") (pin "4") (pinfunction "LID2_4") (pintype "power_in"))
      (node (ref "Q2") (pin "E") (pinfunction "E_E") (pintype "passive"))
      (node (ref "Q3") (pin "E") (pinfunction "E_E") (pintype "passive"))
      (node (ref "Q4") (pin "E") (pinfunction "E_E") (pintype "passive"))
      (node (ref "R20") (pin "1") (pinfunction "1_1") (pintype "passive"))
      (node (ref "R21") (pin "1") (pinfunction "1_1") (pintype "passive"))
      (node (ref "R23") (pin "1") (pinfunction "1_1") (pintype "passive"))
      (node (ref "R45") (pin "2") (pinfunction "2_2") (pintype "passive"))
      (node (ref "R46") (pin "2") (pinfunction "2_2") (pintype "passive"))
      (node (ref "R47") (pin "2") (pinfunction "2_2") (pintype "passive"))
      (node (ref "R5") (pin "2") (pinfunction "2_2") (pintype "passive"))
      (node (ref "SLD_A") (pin "1") (pinfunction "A_1") (pintype "passive"))
      (node (ref "SLD_B") (pin "1") (pinfunction "A_1") (pintype "passive"))
      (node (ref "SLD_C") (pin "1") (pinfunction "A_1") (pintype "passive"))
      (node (ref "SW_A") (pin "1") (pinfunction "1_1") (pintype "passive"))
      (node (ref "SW_A") (pin "2") (pinfunction "2_2") (pintype "passive"))
      (node (ref "SW_B") (pin "1") (pinfunction "1_1") (pintype "passive"))
      (node (ref "SW_B") (pin "2") (pinfunction "2_2") (pintype "passive"))
      (node (ref "SW_C") (pin "1") (pinfunction "1_1") (pintype "passive"))
      (node (ref "SW_C") (pin "2") (pinfunction "2_2") (pintype "passive"))
      (node (ref "U$1") (pin "6") (pinfunction "P$6_6") (pintype "bidirectional"))
      (node (ref "U1") (pin "16") (pinfunction "VSS_2_16") (pintype "power_in"))
      (node (ref "U1") (pin "31") (pinfunction "BOOT0_31") (pintype "input"))
      (node (ref "U1") (pin "32") (pinfunction "VSS_1_32") (pintype "power_in"))
      (node (ref "U2") (pin "10") (pinfunction "+IN_10") (pintype "input"))
      (node (ref "U2") (pin "11") (pinfunction "V-_11") (pintype "power_in"))
      (node (ref "U2") (pin "12") (pinfunction "+IN_12") (pintype "input"))
      (node (ref "U2") (pin "3") (pinfunction "+IN_3") (pintype "input"))
      (node (ref "U2") (pin "5") (pinfunction "+IN_5") (pintype "input"))
      (node (ref "U3") (pin "10") (pinfunction "+IN_10") (pintype "input"))
      (node (ref "U3") (pin "12") (pinfunction "+IN_12") (pintype "input"))
      (node (ref "U3") (pin "3") (pinfunction "+IN_3") (pintype "input"))
      (node (ref "U3") (pin "5") (pinfunction "+IN_5") (pintype "input"))
    )
    (net (code "24") (name "LEDS_SCK") (class "Default")
      (node (ref "IC5") (pin "3") (pinfunction "SCLK_3") (pintype "bidirectional"))
      (node (ref "U1") (pin "26") (pinfunction "PB3_26") (pintype "bidirectional"))
    )
    (net (code "25") (name "LEDS_SIN") (class "Default")
      (node (ref "IC5") (pin "2") (pinfunction "SIN_2") (pintype "bidirectional"))
      (node (ref "U1") (pin "28") (pinfunction "PB5_28") (pintype "bidirectional"))
    )
    (net (code "26") (name "N_U") (class "Default")
      (node (ref "U2") (pin "6") (pinfunction "-IN_6") (pintype "input"))
      (node (ref "U2") (pin "7") (pinfunction "OUT_7") (pintype "output"))
    )
    (net (code "27") (name "Net-(A_OUT_LED-GRN)") (class "Default")
      (node (ref "A_OUT_LED") (pin "GREEN_C") (pinfunction "GRN_GREEN_C") (pintype "bidirectional"))
      (node (ref "IC5") (pin "13") (pinfunction "OUT8_13") (pintype "bidirectional"))
    )
    (net (code "28") (name "Net-(A_OUT_LED-RED)") (class "Default")
      (node (ref "A_OUT_LED") (pin "RED_C") (pinfunction "RED_RED_C") (pintype "bidirectional"))
      (node (ref "IC5") (pin "14") (pinfunction "OUT9_14") (pintype "bidirectional"))
    )
    (net (code "29") (name "Net-(B_OUT_LED-GRN)") (class "Default")
      (node (ref "B_OUT_LED") (pin "GREEN_C") (pinfunction "GRN_GREEN_C") (pintype "bidirectional"))
      (node (ref "IC5") (pin "16") (pinfunction "OUT11_16") (pintype "bidirectional"))
    )
    (net (code "30") (name "Net-(B_OUT_LED-RED)") (class "Default")
      (node (ref "B_OUT_LED") (pin "RED_C") (pinfunction "RED_RED_C") (pintype "bidirectional"))
      (node (ref "IC5") (pin "15") (pinfunction "OUT10_15") (pintype "bidirectional"))
    )
    (net (code "31") (name "Net-(C1-Pad1)") (class "Default")
      (node (ref "C1") (pin "1") (pinfunction "1_1") (pintype "passive"))
      (node (ref "D1") (pin "C") (pinfunction "C_C") (pintype "passive"))
      (node (ref "L1") (pin "1") (pinfunction "1_1") (pintype "passive"))
      (node (ref "L2") (pin "2") (pinfunction "2_2") (pintype "passive"))
      (node (ref "L3") (pin "2") (pinfunction "2_2") (pintype "passive"))
    )
    (net (code "32") (name "Net-(C22-Pad2)") (class "Default")
      (node (ref "C22") (pin "2") (pinfunction "2_2") (pintype "passive"))
      (node (ref "Q1") (pin "1") (pinfunction "1_1") (pintype "passive"))
      (node (ref "R6") (pin "2") (pinfunction "2_2") (pintype "passive"))
    )
    (net (code "33") (name "Net-(C_OUT_LED-GRN)") (class "Default")
      (node (ref "C_OUT_LED") (pin "GREEN_C") (pinfunction "GRN_GREEN_C") (pintype "bidirectional"))
      (node (ref "IC5") (pin "18") (pinfunction "OUT13_18") (pintype "bidirectional"))
    )
    (net (code "34") (name "Net-(C_OUT_LED-RED)") (class "Default")
      (node (ref "C_OUT_LED") (pin "RED_C") (pinfunction "RED_RED_C") (pintype "bidirectional"))
      (node (ref "IC5") (pin "17") (pinfunction "OUT12_17") (pintype "bidirectional"))
    )
    (net (code "35") (name "Net-(D2-PadA)") (class "Default")
      (node (ref "D2") (pin "A") (pinfunction "A_A") (pintype "passive"))
      (node (ref "L4") (pin "2") (pinfunction "2_2") (pintype "passive"))
    )
    (net (code "36") (name "Net-(D3-PadC)") (class "Default")
      (node (ref "D3") (pin "C") (pinfunction "C_C") (pintype "passive"))
      (node (ref "Q2") (pin "B") (pinfunction "B_B") (pintype "passive"))
      (node (ref "R18") (pin "2") (pinfunction "2_2") (pintype "passive"))
      (node (ref "R23") (pin "2") (pinfunction "2_2") (pintype "passive"))
    )
    (net (code "37") (name "Net-(D4-PadC)") (class "Default")
      (node (ref "D4") (pin "C") (pinfunction "C_C") (pintype "passive"))
      (node (ref "Q3") (pin "B") (pinfunction "B_B") (pintype "passive"))
      (node (ref "R19") (pin "2") (pinfunction "2_2") (pintype "passive"))
      (node (ref "R20") (pin "2") (pinfunction "2_2") (pintype "passive"))
    )
    (net (code "38") (name "Net-(D5-PadC)") (class "Default")
      (node (ref "D5") (pin "C") (pinfunction "C_C") (pintype "passive"))
      (node (ref "Q4") (pin "B") (pinfunction "B_B") (pintype "passive"))
      (node (ref "R21") (pin "2") (pinfunction "2_2") (pintype "passive"))
      (node (ref "R22") (pin "2") (pinfunction "2_2") (pintype "passive"))
    )
    (net (code "39") (name "Net-(IC1-VI)") (class "Default")
      (node (ref "C5") (pin "1") (pinfunction "1_1") (pintype "passive"))
      (node (ref "IC1") (pin "1") (pinfunction "VI_1") (pintype "input"))
      (node (ref "L1") (pin "2") (pinfunction "2_2") (pintype "passive"))
    )
    (net (code "40") (name "Net-(IC2-VI)") (class "Default")
      (node (ref "C3") (pin "1") (pinfunction "1_1") (pintype "passive"))
      (node (ref "IC2") (pin "3") (pinfunction "VI_3") (pintype "input"))
      (node (ref "L2") (pin "1") (pinfunction "1_1") (pintype "passive"))
    )
    (net (code "41") (name "Net-(IC4A-X0)") (class "Default")
      (node (ref "IC4") (pin "13") (pinfunction "X0_13") (pintype "bidirectional"))
      (node (ref "POT_C") (pin "P$2") (pinfunction "S_P$2") (pintype "passive"))
    )
    (net (code "42") (name "Net-(IC4A-X1)") (class "Default")
      (node (ref "IC4") (pin "14") (pinfunction "X1_14") (pintype "bidirectional"))
      (node (ref "SLD_C") (pin "2") (pinfunction "S_2") (pintype "passive"))
    )
    (net (code "43") (name "Net-(IC4A-X2)") (class "Default")
      (node (ref "IC4") (pin "15") (pinfunction "X2_15") (pintype "bidirectional"))
      (node (ref "SLD_B") (pin "2") (pinfunction "S_2") (pintype "passive"))
    )
    (net (code "44") (name "Net-(IC4A-X3)") (class "Default")
      (node (ref "IC4") (pin "12") (pinfunction "X3_12") (pintype "bidirectional"))
      (node (ref "POT_A") (pin "P$2") (pinfunction "S_P$2") (pintype "passive"))
    )
    (net (code "45") (name "Net-(IC4A-X4)") (class "Default")
      (node (ref "IC4") (pin "1") (pinfunction "X4_1") (pintype "bidirectional"))
      (node (ref "SLD_A") (pin "2") (pinfunction "S_2") (pintype "passive"))
    )
    (net (code "46") (name "Net-(IC4A-X6)") (class "Default")
      (node (ref "IC4") (pin "2") (pinfunction "X6_2") (pintype "bidirectional"))
      (node (ref "POT_B") (pin "P$2") (pinfunction "S_P$2") (pintype "passive"))
    )
    (net (code "47") (name "Net-(IC5-IREF)") (class "Default")
      (node (ref "IC5") (pin "23") (pinfunction "IREF_23") (pintype "bidirectional"))
      (node (ref "R5") (pin "1") (pinfunction "1_1") (pintype "passive"))
    )
    (net (code "48") (name "Net-(IC5-OUT1)") (class "Default")
      (node (ref "IC5") (pin "6") (pinfunction "OUT1_6") (pintype "bidirectional"))
      (node (ref "R15") (pin "2") (pinfunction "2_2") (pintype "passive"))
    )
    (net (code "49") (name "Net-(IC5-OUT2)") (class "Default")
      (node (ref "IC5") (pin "7") (pinfunction "OUT2_7") (pintype "bidirectional"))
      (node (ref "MODE_C") (pin "RED_C") (pinfunction "RED_RED_C") (pintype "bidirectional"))
    )
    (net (code "50") (name "Net-(IC5-OUT3)") (class "Default")
      (node (ref "IC5") (pin "8") (pinfunction "OUT3_8") (pintype "bidirectional"))
      (node (ref "MODE_C") (pin "GREEN_C") (pinfunction "GRN_GREEN_C") (pintype "bidirectional"))
    )
    (net (code "51") (name "Net-(IC5-OUT4)") (class "Default")
      (node (ref "IC5") (pin "9") (pinfunction "OUT4_9") (pintype "bidirectional"))
      (node (ref "MODE_A") (pin "GREEN_C") (pinfunction "GRN_GREEN_C") (pintype "bidirectional"))
    )
    (net (code "52") (name "Net-(IC5-OUT5)") (class "Default")
      (node (ref "IC5") (pin "10") (pinfunction "OUT5_10") (pintype "bidirectional"))
      (node (ref "MODE_A") (pin "RED_C") (pinfunction "RED_RED_C") (pintype "bidirectional"))
    )
    (net (code "53") (name "Net-(IC5-OUT6)") (class "Default")
      (node (ref "IC5") (pin "11") (pinfunction "OUT6_11") (pintype "bidirectional"))
      (node (ref "MODE_B") (pin "GREEN_C") (pinfunction "GRN_GREEN_C") (pintype "bidirectional"))
    )
    (net (code "54") (name "Net-(IC5-OUT7)") (class "Default")
      (node (ref "IC5") (pin "12") (pinfunction "OUT7_12") (pintype "bidirectional"))
      (node (ref "MODE_B") (pin "RED_C") (pinfunction "RED_RED_C") (pintype "bidirectional"))
    )
    (net (code "55") (name "Net-(IC5-OUT14)") (class "Default")
      (node (ref "IC5") (pin "19") (pinfunction "OUT14_19") (pintype "bidirectional"))
      (node (ref "R16") (pin "2") (pinfunction "2_2") (pintype "passive"))
    )
    (net (code "56") (name "Net-(IC5-OUT15)") (class "Default")
      (node (ref "IC5") (pin "20") (pinfunction "OUT15_20") (pintype "bidirectional"))
      (node (ref "R17") (pin "2") (pinfunction "2_2") (pintype "passive"))
    )
    (net (code "57") (name "Net-(IC5-VCC)") (class "Default")
      (node (ref "C14") (pin "1") (pinfunction "1_1") (pintype "passive"))
      (node (ref "C15") (pin "1") (pinfunction "1_1") (pintype "passive"))
      (node (ref "IC5") (pin "24") (pinfunction "VCC_24") (pintype "bidirectional"))
      (node (ref "L5") (pin "1") (pinfunction "1_1") (pintype "passive"))
    )
    (net (code "58") (name "Net-(IC6A-+IN)") (class "Default")
      (node (ref "IC6") (pin "3") (pinfunction "+IN_3") (pintype "input"))
      (node (ref "R44") (pin "2") (pinfunction "2_2") (pintype "passive"))
      (node (ref "R47") (pin "1") (pinfunction "1_1") (pintype "passive"))
    )
    (net (code "59") (name "Net-(IC6A--IN)") (class "Default")
      (node (ref "IC6") (pin "2") (pinfunction "-IN_2") (pintype "input"))
      (node (ref "R13") (pin "1") (pinfunction "1_1") (pintype "passive"))
    )
    (net (code "60") (name "Net-(IC6A-OUT)") (class "Default")
      (node (ref "IC6") (pin "1") (pinfunction "OUT_1") (pintype "output"))
      (node (ref "R39") (pin "2") (pinfunction "2_2") (pintype "passive"))
      (node (ref "R44") (pin "1") (pinfunction "1_1") (pintype "passive"))
    )
    (net (code "61") (name "Net-(IC6B-+IN)") (class "Default")
      (node (ref "IC6") (pin "5") (pinfunction "+IN_5") (pintype "input"))
      (node (ref "R41") (pin "2") (pinfunction "2_2") (pintype "passive"))
      (node (ref "R46") (pin "1") (pinfunction "1_1") (pintype "passive"))
    )
    (net (code "62") (name "Net-(IC6B--IN)") (class "Default")
      (node (ref "IC6") (pin "6") (pinfunction "-IN_6") (pintype "input"))
      (node (ref "R12") (pin "1") (pinfunction "1_1") (pintype "passive"))
    )
    (net (code "63") (name "Net-(IC6B-OUT)") (class "Default")
      (node (ref "IC6") (pin "7") (pinfunction "OUT_7") (pintype "output"))
      (node (ref "R38") (pin "2") (pinfunction "2_2") (pintype "passive"))
      (node (ref "R41") (pin "1") (pinfunction "1_1") (pintype "passive"))
    )
    (net (code "64") (name "Net-(IC6C-+IN)") (class "Default")
      (node (ref "IC6") (pin "10") (pinfunction "+IN_10") (pintype "input"))
      (node (ref "R36") (pin "2") (pinfunction "2_2") (pintype "passive"))
      (node (ref "R45") (pin "1") (pinfunction "1_1") (pintype "passive"))
    )
    (net (code "65") (name "Net-(IC6C--IN)") (class "Default")
      (node (ref "IC6") (pin "9") (pinfunction "-IN_9") (pintype "input"))
      (node (ref "R11") (pin "1") (pinfunction "1_1") (pintype "passive"))
    )
    (net (code "66") (name "Net-(IC6C-OUT)") (class "Default")
      (node (ref "IC6") (pin "8") (pinfunction "OUT_8") (pintype "output"))
      (node (ref "R36") (pin "1") (pinfunction "1_1") (pintype "passive"))
      (node (ref "R37") (pin "2") (pinfunction "2_2") (pintype "passive"))
    )
    (net (code "67") (name "Net-(IC6D--IN)") (class "Default")
      (node (ref "IC6") (pin "13") (pinfunction "-IN_13") (pintype "input"))
      (node (ref "IC6") (pin "14") (pinfunction "OUT_14") (pintype "output"))
    )
    (net (code "68") (name "Net-(J4-3)") (class "Default")
      (node (ref "J4") (pin "P3") (pinfunction "3_P3") (pintype "passive"))
      (node (ref "R24") (pin "2") (pinfunction "2_2") (pintype "passive"))
    )
    (net (code "69") (name "Net-(J6-3)") (class "Default")
      (node (ref "J6") (pin "P3") (pinfunction "3_P3") (pintype "passive"))
      (node (ref "R26") (pin "2") (pinfunction "2_2") (pintype "passive"))
    )
    (net (code "70") (name "Net-(J7-3)") (class "Default")
      (node (ref "J7") (pin "P3") (pinfunction "3_P3") (pintype "passive"))
      (node (ref "R37") (pin "1") (pinfunction "1_1") (pintype "passive"))
    )
    (net (code "71") (name "Net-(J8-3)") (class "Default")
      (node (ref "J8") (pin "P3") (pinfunction "3_P3") (pintype "passive"))
      (node (ref "R38") (pin "1") (pinfunction "1_1") (pintype "passive"))
    )
    (net (code "72") (name "Net-(J9-3)") (class "Default")
      (node (ref "J9") (pin "P3") (pinfunction "3_P3") (pintype "passive"))
      (node (ref "R39") (pin "1") (pinfunction "1_1") (pintype "passive"))
    )
    (net (code "73") (name "Net-(J10-3)") (class "Default")
      (node (ref "J10") (pin "P3") (pinfunction "3_P3") (pintype "passive"))
      (node (ref "R35") (pin "1") (pinfunction "1_1") (pintype "passive"))
      (node (ref "R40") (pin "1") (pinfunction "1_1") (pintype "passive"))
    )
    (net (code "74") (name "Net-(J11-3)") (class "Default")
      (node (ref "J11") (pin "P3") (pinfunction "3_P3") (pintype "passive"))
      (node (ref "R29") (pin "1") (pinfunction "1_1") (pintype "passive"))
      (node (ref "R42") (pin "1") (pinfunction "1_1") (pintype "passive"))
    )
    (net (code "75") (name "Net-(J12-3)") (class "Default")
      (node (ref "J12") (pin "P3") (pinfunction "3_P3") (pintype "passive"))
      (node (ref "R32") (pin "1") (pinfunction "1_1") (pintype "passive"))
      (node (ref "R43") (pin "1") (pinfunction "1_1") (pintype "passive"))
    )
    (net (code "76") (name "Net-(Q1B-2)") (class "Default")
      (node (ref "C21") (pin "2") (pinfunction "2_2") (pintype "passive"))
      (node (ref "Q1") (pin "3") (pinfunction "2_3") (pintype "passive"))
      (node (ref "R9") (pin "2") (pinfunction "2_2") (pintype "passive"))
    )
    (net (code "77") (name "Net-(SLD_AA-C)") (class "Default")
      (node (ref "R16") (pin "1") (pinfunction "1_1") (pintype "passive"))
      (node (ref "SLD_A") (pin "E") (pinfunction "C_E") (pintype "passive"))
    )
    (net (code "78") (name "Net-(SLD_BA-C)") (class "Default")
      (node (ref "R17") (pin "1") (pinfunction "1_1") (pintype "passive"))
      (node (ref "SLD_B") (pin "E") (pinfunction "C_E") (pintype "passive"))
    )
    (net (code "79") (name "Net-(SLD_CA-C)") (class "Default")
      (node (ref "R15") (pin "1") (pinfunction "1_1") (pintype "passive"))
      (node (ref "SLD_C") (pin "E") (pinfunction "C_E") (pintype "passive"))
    )
    (net (code "80") (name "Net-(U1-PF0{slash}OSC_IN)") (class "Default")
      (node (ref "R9") (pin "1") (pinfunction "1_1") (pintype "passive"))
      (node (ref "U1") (pin "2") (pinfunction "PF0/OSC_IN_2") (pintype "bidirectional"))
    )
    (net (code "81") (name "Net-(U1-PF1{slash}OSC_OUT)") (class "Default")
      (node (ref "R6") (pin "1") (pinfunction "1_1") (pintype "passive"))
      (node (ref "U1") (pin "3") (pinfunction "PF1/OSC_OUT_3") (pintype "bidirectional"))
    )
    (net (code "82") (name "Net-(U2A--IN)") (class "Default")
      (node (ref "C30") (pin "1") (pinfunction "1_1") (pintype "passive"))
      (node (ref "R14") (pin "2") (pinfunction "2_2") (pintype "passive"))
      (node (ref "R2") (pin "1") (pinfunction "1_1") (pintype "passive"))
      (node (ref "R26") (pin "1") (pinfunction "1_1") (pintype "passive"))
      (node (ref "U2") (pin "2") (pinfunction "-IN_2") (pintype "input"))
    )
    (net (code "83") (name "Net-(U2C--IN)") (class "Default")
      (node (ref "C23") (pin "1") (pinfunction "1_1") (pintype "passive"))
      (node (ref "R25") (pin "1") (pinfunction "1_1") (pintype "passive"))
      (node (ref "R3") (pin "1") (pinfunction "1_1") (pintype "passive"))
      (node (ref "R7") (pin "2") (pinfunction "2_2") (pintype "passive"))
      (node (ref "U2") (pin "9") (pinfunction "-IN_9") (pintype "input"))
    )
    (net (code "84") (name "Net-(U2D--IN)") (class "Default")
      (node (ref "C24") (pin "1") (pinfunction "1_1") (pintype "passive"))
      (node (ref "R24") (pin "1") (pinfunction "1_1") (pintype "passive"))
      (node (ref "R4") (pin "1") (pinfunction "1_1") (pintype "passive"))
      (node (ref "R8") (pin "2") (pinfunction "2_2") (pintype "passive"))
      (node (ref "U2") (pin "13") (pinfunction "-IN_13") (pintype "input"))
    )
    (net (code "85") (name "Net-(U3A--IN)") (class "Default")
      (node (ref "C33") (pin "1") (pinfunction "1_1") (pintype "passive"))
      (node (ref "R30") (pin "1") (pinfunction "1_1") (pintype "passive"))
      (node (ref "R31") (pin "1") (pinfunction "1_1") (pintype "passive"))
      (node (ref "R32") (pin "2") (pinfunction "2_2") (pintype "passive"))
      (node (ref "U3") (pin "2") (pinfunction "-IN_2") (pintype "input"))
    )
    (net (code "86") (name "Net-(U3A-OUT)") (class "Default")
      (node (ref "C33") (pin "2") (pinfunction "2_2") (pintype "passive"))
      (node (ref "R43") (pin "2") (pinfunction "2_2") (pintype "passive"))
      (node (ref "U3") (pin "1") (pinfunction "OUT_1") (pintype "output"))
    )
    (net (code "87") (name "Net-(U3B--IN)") (class "Default")
      (node (ref "C32") (pin "1") (pinfunction "1_1") (pintype "passive"))
      (node (ref "R27") (pin "1") (pinfunction "1_1") (pintype "passive"))
      (node (ref "R28") (pin "1") (pinfunction "1_1") (pintype "passive"))
      (node (ref "R29") (pin "2") (pinfunction "2_2") (pintype "passive"))
      (node (ref "U3") (pin "6") (pinfunction "-IN_6") (pintype "input"))
    )
    (net (code "88") (name "Net-(U3B-OUT)") (class "Default")
      (node (ref "C32") (pin "2") (pinfunction "2_2") (pintype "passive"))
      (node (ref "R42") (pin "2") (pinfunction "2_2") (pintype "passive"))
      (node (ref "U3") (pin "7") (pinfunction "OUT_7") (pintype "output"))
    )
    (net (code "89") (name "Net-(U3C--IN)") (class "Default")
      (node (ref "C34") (pin "1") (pinfunction "1_1") (pintype "passive"))
      (node (ref "R33") (pin "1") (pinfunction "1_1") (pintype "passive"))
      (node (ref "R34") (pin "1") (pinfunction "1_1") (pintype "passive"))
      (node (ref "R35") (pin "2") (pinfunction "2_2") (pintype "passive"))
      (node (ref "U3") (pin "9") (pinfunction "-IN_9") (pintype "input"))
    )
    (net (code "90") (name "Net-(U3C-OUT)") (class "Default")
      (node (ref "C34") (pin "2") (pinfunction "2_2") (pintype "passive"))
      (node (ref "R40") (pin "2") (pinfunction "2_2") (pintype "passive"))
      (node (ref "U3") (pin "8") (pinfunction "OUT_8") (pintype "output"))
    )
    (net (code "91") (name "Net-(U3D--IN)") (class "Default")
      (node (ref "U3") (pin "13") (pinfunction "-IN_13") (pintype "input"))
      (node (ref "U3") (pin "14") (pinfunction "OUT_14") (pintype "output"))
    )
    (net (code "92") (name "POTS_ADDR_A") (class "Default")
      (node (ref "IC4") (pin "11") (pinfunction "A_11") (pintype "input"))
      (node (ref "U1") (pin "13") (pinfunction "PA7_13") (pintype "bidirectional"))
    )
    (net (code "93") (name "POTS_ADDR_B") (class "Default")
      (node (ref "IC4") (pin "10") (pinfunction "B_10") (pintype "input"))
      (node (ref "U1") (pin "18") (pinfunction "PA8_18") (pintype "bidirectional"))
    )
    (net (code "94") (name "POTS_ADDR_C") (class "Default")
      (node (ref "IC4") (pin "9") (pinfunction "C_9") (pintype "input"))
      (node (ref "U1") (pin "19") (pinfunction "PA9_19") (pintype "bidirectional"))
    )
    (net (code "95") (name "RESET") (class "Default")
      (node (ref "C28") (pin "1") (pinfunction "1_1") (pintype "passive"))
      (node (ref "JP2") (pin "4") (pinfunction "4_4") (pintype "passive"))
      (node (ref "R10") (pin "2") (pinfunction "2_2") (pintype "passive"))
      (node (ref "U1") (pin "4") (pinfunction "NRST_4") (pintype "bidirectional"))
    )
    (net (code "96") (name "SWCLK") (class "Default")
      (node (ref "JP2") (pin "3") (pinfunction "3_3") (pintype "passive"))
      (node (ref "U1") (pin "24") (pinfunction "PA14_24") (pintype "bidirectional"))
    )
    (net (code "97") (name "SWDIO") (class "Default")
      (node (ref "JP2") (pin "2") (pinfunction "2_2") (pintype "passive"))
      (node (ref "U1") (pin "23") (pinfunction "PA13_23") (pintype "bidirectional"))
    )
    (net (code "98") (name "SW_MODE_A") (class "Default")
      (node (ref "SW_A") (pin "3") (pinfunction "3_3") (pintype "passive"))
      (node (ref "SW_A") (pin "4") (pinfunction "4_4") (pintype "passive"))
      (node (ref "U1") (pin "27") (pinfunction "PB4_27") (pintype "bidirectional"))
    )
    (net (code "99") (name "SW_MODE_B") (class "Default")
      (node (ref "SW_B") (pin "3") (pinfunction "3_3") (pintype "passive"))
      (node (ref "SW_B") (pin "4") (pinfunction "4_4") (pintype "passive"))
      (node (ref "U1") (pin "29") (pinfunction "PB6_29") (pintype "bidirectional"))
    )
    (net (code "100") (name "SW_MODE_C") (class "Default")
      (node (ref "SW_C") (pin "3") (pinfunction "3_3") (pintype "passive"))
      (node (ref "SW_C") (pin "4") (pinfunction "4_4") (pintype "passive"))
      (node (ref "U1") (pin "30") (pinfunction "PB7_30") (pintype "bidirectional"))
    )
    (net (code "101") (name "VCC") (class "Default")
      (node (ref "C2") (pin "1") (pinfunction "1_1") (pintype "passive"))
      (node (ref "C31") (pin "1") (pinfunction "1_1") (pintype "passive"))
      (node (ref "C35") (pin "1") (pinfunction "1_1") (pintype "passive"))
      (node (ref "C4") (pin "1") (pinfunction "1_1") (pintype "passive"))
      (node (ref "IC6") (pin "4") (pinfunction "V+_4") (pintype "power_in"))
      (node (ref "L3") (pin "1") (pinfunction "1_1") (pintype "passive"))
      (node (ref "U$1") (pin "1") (pinfunction "P$1_1") (pintype "bidirectional"))
      (node (ref "U3") (pin "4") (pinfunction "V+_4") (pintype "power_in"))
    )
    (net (code "102") (name "VEE") (class "Default")
      (node (ref "C10") (pin "2") (pinfunction "2_2") (pintype "passive"))
      (node (ref "C25") (pin "2") (pinfunction "2_2") (pintype "passive"))
      (node (ref "C9") (pin "2") (pinfunction "2_2") (pintype "passive"))
      (node (ref "L4") (pin "1") (pinfunction "1_1") (pintype "passive"))
      (node (ref "R1") (pin "1") (pinfunction "1_1") (pintype "passive"))
      (node (ref "U$1") (pin "2") (pinfunction "P$2_2") (pintype "bidirectional"))
      (node (ref "U3") (pin "11") (pinfunction "V-_11") (pintype "power_in"))
    )
    (net (code "103") (name "unconnected-(IC4A-X5-Pad5)") (class "Default")
      (node (ref "IC4") (pin "5") (pinfunction "X5_5") (pintype "bidirectional"))
    )
    (net (code "104") (name "unconnected-(IC4A-X7-Pad4)") (class "Default")
      (node (ref "IC4") (pin "4") (pinfunction "X7_4") (pintype "bidirectional"))
    )
    (net (code "105") (name "unconnected-(IC5-LAT-Pad4)") (class "Default")
      (node (ref "IC5") (pin "4") (pinfunction "LAT_4") (pintype "bidirectional"))
    )
    (net (code "106") (name "unconnected-(IC5-OUT0-Pad5)") (class "Default")
      (node (ref "IC5") (pin "5") (pinfunction "OUT0_5") (pintype "bidirectional"))
    )
    (net (code "107") (name "unconnected-(IC5-SOUT-Pad22)") (class "Default")
      (node (ref "IC5") (pin "22") (pinfunction "SOUT_22") (pintype "bidirectional"))
    )
    (net (code "108") (name "unconnected-(J7-2-PadP2)") (class "Default")
      (node (ref "J7") (pin "P2") (pinfunction "2_P2") (pintype "passive"))
    )
    (net (code "109") (name "unconnected-(J8-2-PadP2)") (class "Default")
      (node (ref "J8") (pin "P2") (pinfunction "2_P2") (pintype "passive"))
    )
    (net (code "110") (name "unconnected-(J9-2-PadP2)") (class "Default")
      (node (ref "J9") (pin "P2") (pinfunction "2_P2") (pintype "passive"))
    )
    (net (code "111") (name "unconnected-(J10-2-PadP2)") (class "Default")
      (node (ref "J10") (pin "P2") (pinfunction "2_P2") (pintype "passive"))
    )
    (net (code "112") (name "unconnected-(J11-2-PadP2)") (class "Default")
      (node (ref "J11") (pin "P2") (pinfunction "2_P2") (pintype "passive"))
    )
    (net (code "113") (name "unconnected-(J12-2-PadP2)") (class "Default")
      (node (ref "J12") (pin "P2") (pinfunction "2_P2") (pintype "passive"))
    )
  )
)
